# BrainPadWiFi.net
KiCad netlist of a schematic drawn in EAGLE
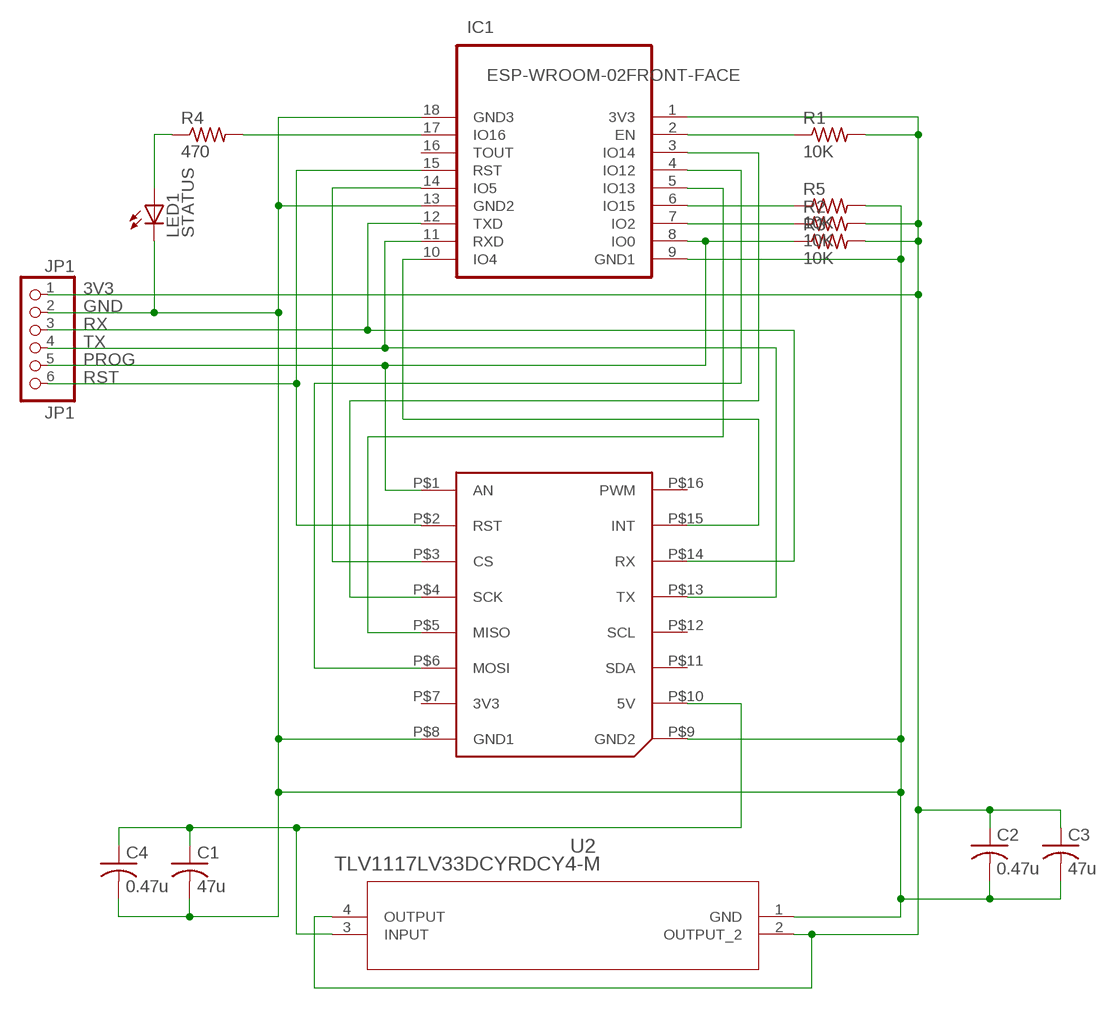
[diagram p0: schematic, sheet 1]

(export (version "E")
  (design (tool "Eeschema 10.0.6"))
  (components
    (comp (ref "C1")
      (value "47u")
      (footprint "eagle-import:C1206")
      (libsource (lib "eagle-import") (part "C-USC1206"))
    )
    (comp (ref "C2")
      (value "0.47u")
      (footprint "eagle-import:C1206")
      (libsource (lib "eagle-import") (part "C-USC1206"))
    )
    (comp (ref "C3")
      (value "47u")
      (footprint "eagle-import:C1206")
      (libsource (lib "eagle-import") (part "C-USC1206"))
    )
    (comp (ref "C4")
      (value "0.47u")
      (footprint "eagle-import:C1206")
      (libsource (lib "eagle-import") (part "C-USC1206"))
    )
    (comp (ref "IC1")
      (value "ESP-WROOM-02FRONT-FACE")
      (footprint "eagle-import:FRONT-FACE")
      (libsource (lib "eagle-import") (part "ESP-WROOM-02FRONT-FACE"))
    )
    (comp (ref "JP1")
      (value "JP1")
      (footprint "eagle-import:1X06")
      (libsource (lib "eagle-import") (part "PINHD-1X6"))
    )
    (comp (ref "LED1")
      (value "STATUS")
      (footprint "eagle-import:SML1206")
      (libsource (lib "eagle-import") (part "LEDSML1206"))
    )
    (comp (ref "R1")
      (value "10K")
      (footprint "eagle-import:R1206")
      (libsource (lib "eagle-import") (part "R-US_R1206"))
    )
    (comp (ref "R2")
      (value "10K")
      (footprint "eagle-import:R1206")
      (libsource (lib "eagle-import") (part "R-US_R1206"))
    )
    (comp (ref "R3")
      (value "10K")
      (footprint "eagle-import:R1206")
      (libsource (lib "eagle-import") (part "R-US_R1206"))
    )
    (comp (ref "R4")
      (value "470")
      (footprint "eagle-import:R1206")
      (libsource (lib "eagle-import") (part "R-US_R1206"))
    )
    (comp (ref "R5")
      (value "10K")
      (footprint "eagle-import:R1206")
      (libsource (lib "eagle-import") (part "R-US_R1206"))
    )
    (comp (ref "U$1")
      (value "MIKROE_CLICKMINI")
      (footprint "eagle-import:MIKROE_BUS_MINI")
      (libsource (lib "eagle-import") (part "MIKROE_CLICKMINI"))
    )
    (comp (ref "U2")
      (value "TLV1117LV33DCYRDCY4-M")
      (footprint "eagle-import:DCY4-M")
      (fields (field (name "MANUFACTURER_PART_NUMBER") "TLV1117LV33DCYR"))
      (libsource (lib "eagle-import") (part "TLV1117LV33DCYRDCY4-M"))
    )
  )
  (nets
    (net (code "1") (name "/3V3") (class "Default")
      (node (ref "C2") (pin "1") (pinfunction "1_1") (pintype "passive"))
      (node (ref "C3") (pin "1") (pinfunction "1_1") (pintype "passive"))
      (node (ref "IC1") (pin "1") (pinfunction "3V3_1") (pintype "power_in"))
      (node (ref "JP1") (pin "1") (pinfunction "1_1") (pintype "passive"))
      (node (ref "R1") (pin "2") (pinfunction "2_2") (pintype "passive"))
      (node (ref "R2") (pin "2") (pinfunction "2_2") (pintype "passive"))
      (node (ref "R3") (pin "2") (pinfunction "2_2") (pintype "passive"))
      (node (ref "U2") (pin "2") (pinfunction "OUTPUT_2_2") (pintype "output"))
      (node (ref "U2") (pin "4") (pinfunction "OUTPUT_4") (pintype "output"))
    )
    (net (code "2") (name "/GND") (class "Default")
      (node (ref "C1") (pin "2") (pinfunction "2_2") (pintype "passive"))
      (node (ref "C2") (pin "2") (pinfunction "2_2") (pintype "passive"))
      (node (ref "C3") (pin "2") (pinfunction "2_2") (pintype "passive"))
      (node (ref "C4") (pin "2") (pinfunction "2_2") (pintype "passive"))
      (node (ref "IC1") (pin "13") (pinfunction "GND2_13") (pintype "power_in"))
      (node (ref "IC1") (pin "18") (pinfunction "GND3_18") (pintype "power_in"))
      (node (ref "IC1") (pin "9") (pinfunction "GND1_9") (pintype "power_in"))
      (node (ref "JP1") (pin "2") (pinfunction "2_2") (pintype "passive"))
      (node (ref "LED1") (pin "C") (pinfunction "C_C") (pintype "passive"))
      (node (ref "R5") (pin "2") (pinfunction "2_2") (pintype "passive"))
      (node (ref "U$1") (pin "P$8") (pinfunction "GND1_P$8") (pintype "bidirectional"))
      (node (ref "U$1") (pin "P$9") (pinfunction "GND2_P$9") (pintype "bidirectional"))
      (node (ref "U2") (pin "1") (pinfunction "GND_1") (pintype "passive"))
    )
    (net (code "3") (name "/PROG") (class "Default")
      (node (ref "IC1") (pin "8") (pinfunction "IO0_8") (pintype "bidirectional"))
      (node (ref "JP1") (pin "5") (pinfunction "5_5") (pintype "passive"))
      (node (ref "R3") (pin "1") (pinfunction "1_1") (pintype "passive"))
      (node (ref "U$1") (pin "P$1") (pinfunction "AN_P$1") (pintype "bidirectional"))
    )
    (net (code "4") (name "/RST") (class "Default")
      (node (ref "IC1") (pin "15") (pinfunction "RST_15") (pintype "bidirectional"))
      (node (ref "JP1") (pin "6") (pinfunction "6_6") (pintype "passive"))
      (node (ref "U$1") (pin "P$2") (pinfunction "RST_P$2") (pintype "bidirectional"))
    )
    (net (code "5") (name "/RX") (class "Default")
      (node (ref "IC1") (pin "12") (pinfunction "TXD_12") (pintype "bidirectional"))
      (node (ref "JP1") (pin "3") (pinfunction "3_3") (pintype "passive"))
      (node (ref "U$1") (pin "P$14") (pinfunction "RX_P$14") (pintype "bidirectional"))
    )
    (net (code "6") (name "/TX") (class "Default")
      (node (ref "IC1") (pin "11") (pinfunction "RXD_11") (pintype "bidirectional"))
      (node (ref "JP1") (pin "4") (pinfunction "4_4") (pintype "passive"))
      (node (ref "U$1") (pin "P$13") (pinfunction "TX_P$13") (pintype "bidirectional"))
    )
    (net (code "7") (name "Net-(IC1-EN)") (class "Default")
      (node (ref "IC1") (pin "2") (pinfunction "EN_2") (pintype "bidirectional"))
      (node (ref "R1") (pin "1") (pinfunction "1_1") (pintype "passive"))
    )
    (net (code "8") (name "Net-(IC1-IO2)") (class "Default")
      (node (ref "IC1") (pin "7") (pinfunction "IO2_7") (pintype "bidirectional"))
      (node (ref "R2") (pin "1") (pinfunction "1_1") (pintype "passive"))
    )
    (net (code "9") (name "Net-(IC1-IO4)") (class "Default")
      (node (ref "IC1") (pin "10") (pinfunction "IO4_10") (pintype "bidirectional"))
      (node (ref "U$1") (pin "P$15") (pinfunction "INT_P$15") (pintype "bidirectional"))
    )
    (net (code "10") (name "Net-(IC1-IO5)") (class "Default")
      (node (ref "IC1") (pin "14") (pinfunction "IO5_14") (pintype "open_collector"))
      (node (ref "U$1") (pin "P$3") (pinfunction "CS_P$3") (pintype "bidirectional"))
    )
    (net (code "11") (name "Net-(IC1-IO12)") (class "Default")
      (node (ref "IC1") (pin "4") (pinfunction "IO12_4") (pintype "bidirectional"))
      (node (ref "U$1") (pin "P$6") (pinfunction "MOSI_P$6") (pintype "bidirectional"))
    )
    (net (code "12") (name "Net-(IC1-IO13)") (class "Default")
      (node (ref "IC1") (pin "5") (pinfunction "IO13_5") (pintype "bidirectional"))
      (node (ref "U$1") (pin "P$5") (pinfunction "MISO_P$5") (pintype "bidirectional"))
    )
    (net (code "13") (name "Net-(IC1-IO14)") (class "Default")
      (node (ref "IC1") (pin "3") (pinfunction "IO14_3") (pintype "bidirectional"))
      (node (ref "U$1") (pin "P$4") (pinfunction "SCK_P$4") (pintype "bidirectional"))
    )
    (net (code "14") (name "Net-(IC1-IO15)") (class "Default")
      (node (ref "IC1") (pin "6") (pinfunction "IO15_6") (pintype "bidirectional"))
      (node (ref "R5") (pin "1") (pinfunction "1_1") (pintype "passive"))
    )
    (net (code "15") (name "Net-(IC1-IO16)") (class "Default")
      (node (ref "IC1") (pin "17") (pinfunction "IO16_17") (pintype "bidirectional"))
      (node (ref "R4") (pin "2") (pinfunction "2_2") (pintype "passive"))
    )
    (net (code "16") (name "Net-(LED1-PadA)") (class "Default")
      (node (ref "LED1") (pin "A") (pinfunction "A_A") (pintype "passive"))
      (node (ref "R4") (pin "1") (pinfunction "1_1") (pintype "passive"))
    )
    (net (code "17") (name "Net-(U$1-5V)") (class "Default")
      (node (ref "C1") (pin "1") (pinfunction "1_1") (pintype "passive"))
      (node (ref "C4") (pin "1") (pinfunction "1_1") (pintype "passive"))
      (node (ref "U$1") (pin "P$10") (pinfunction "5V_P$10") (pintype "bidirectional"))
      (node (ref "U2") (pin "3") (pinfunction "INPUT_3") (pintype "input"))
    )
    (net (code "18") (name "unconnected-(IC1-TOUT-Pad16)") (class "Default")
      (node (ref "IC1") (pin "16") (pinfunction "TOUT_16") (pintype "bidirectional"))
    )
    (net (code "19") (name "unconnected-(U$1-3V3-PadP$7)") (class "Default")
      (node (ref "U$1") (pin "P$7") (pinfunction "3V3_P$7") (pintype "bidirectional"))
    )
    (net (code "20") (name "unconnected-(U$1-PWM-PadP$16)") (class "Default")
      (node (ref "U$1") (pin "P$16") (pinfunction "PWM_P$16") (pintype "bidirectional"))
    )
    (net (code "21") (name "unconnected-(U$1-SCL-PadP$12)") (class "Default")
      (node (ref "U$1") (pin "P$12") (pinfunction "SCL_P$12") (pintype "bidirectional"))
    )
    (net (code "22") (name "unconnected-(U$1-SDA-PadP$11)") (class "Default")
      (node (ref "U$1") (pin "P$11") (pinfunction "SDA_P$11") (pintype "bidirectional"))
    )
  )
)
